# ArduinoCurveTracer3_V1.net
KiCad netlist of a schematic drawn in EAGLE
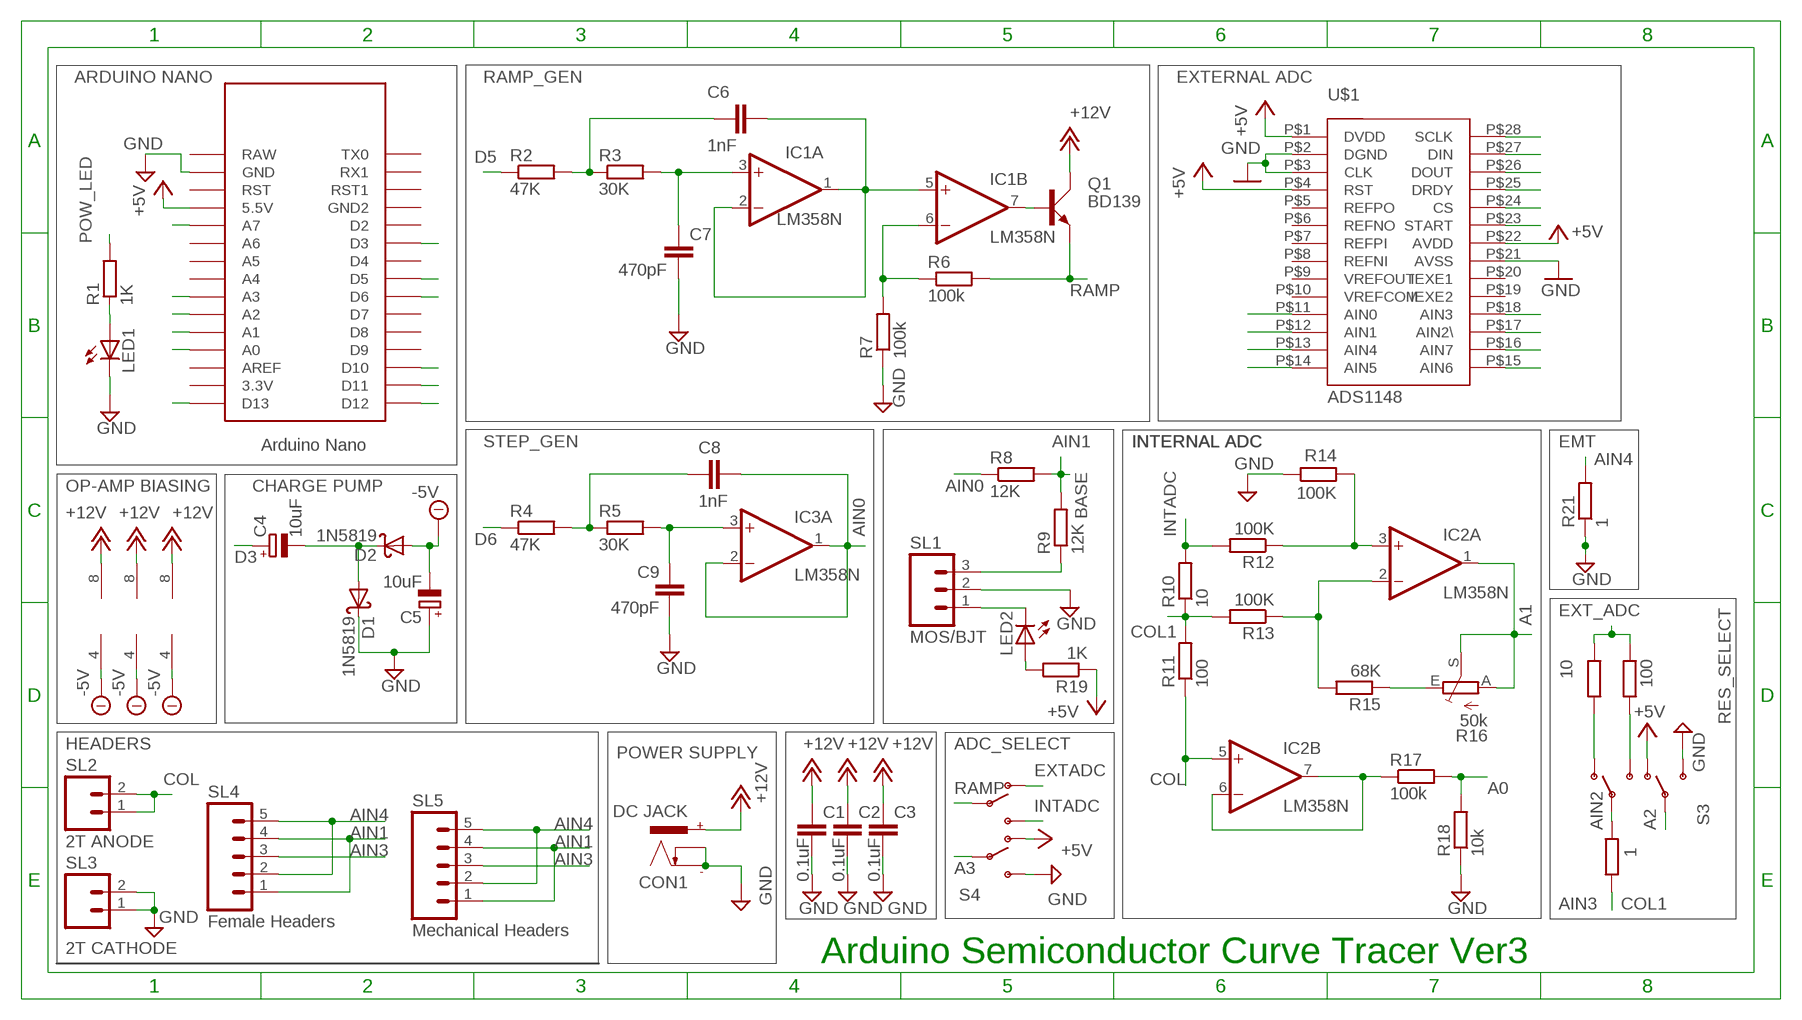
[diagram p0: schematic, sheet 1]

(export (version "E")
  (design (tool "Eeschema 10.0.6"))
  (components
    (comp (ref "ARDUINONANO")
      (value "NANO")
      (footprint "eagle-import:NANO")
      (libsource (lib "eagle-import") (part "NANO"))
    )
    (comp (ref "C1")
      (value "0.1uF")
      (footprint "eagle-import:C0805")
      (libsource (lib "eagle-import") (part "C-EUC0805"))
    )
    (comp (ref "C2")
      (value "0.1uF")
      (footprint "eagle-import:C0805")
      (libsource (lib "eagle-import") (part "C-EUC0805"))
    )
    (comp (ref "C3")
      (value "0.1uF")
      (footprint "eagle-import:C0805")
      (libsource (lib "eagle-import") (part "C-EUC0805"))
    )
    (comp (ref "C4")
      (value "10uF")
      (footprint "eagle-import:E2,5-5")
      (libsource (lib "eagle-import") (part "CPOL-EUE2.5-5"))
    )
    (comp (ref "C5")
      (value "10uF")
      (footprint "eagle-import:E2,5-5")
      (libsource (lib "eagle-import") (part "CPOL-EUE2.5-5"))
    )
    (comp (ref "C6")
      (value "1nF")
      (footprint "eagle-import:C0603")
      (libsource (lib "eagle-import") (part "C-EUC0603"))
    )
    (comp (ref "C7")
      (value "470pF")
      (footprint "eagle-import:C025-024X044")
      (libsource (lib "eagle-import") (part "C-EU025-024X044"))
    )
    (comp (ref "C8")
      (value "1nF")
      (footprint "eagle-import:C025-024X044")
      (libsource (lib "eagle-import") (part "C-EU025-024X044"))
    )
    (comp (ref "C9")
      (value "470pF")
      (footprint "eagle-import:C0805")
      (libsource (lib "eagle-import") (part "C-EUC0805"))
    )
    (comp (ref "CON1")
      (value "DC JACK")
      (footprint "eagle-import:NEB21R")
      (libsource (lib "eagle-import") (part "POWER_CON"))
    )
    (comp (ref "D1")
      (value "1N5819")
      (footprint "eagle-import:DO41-10")
      (libsource (lib "eagle-import") (part "1N5819"))
    )
    (comp (ref "D2")
      (value "1N5819")
      (footprint "eagle-import:DO41-10")
      (libsource (lib "eagle-import") (part "1N5819"))
    )
    (comp (ref "IC1")
      (value "LM358N")
      (footprint "eagle-import:DIL08")
      (libsource (lib "eagle-import") (part "LM358N"))
    )
    (comp (ref "IC2")
      (value "LM358N")
      (footprint "eagle-import:DIL08")
      (libsource (lib "eagle-import") (part "LM358N"))
    )
    (comp (ref "IC3")
      (value "LM358N")
      (footprint "eagle-import:DIL08")
      (libsource (lib "eagle-import") (part "LM358N"))
    )
    (comp (ref "LED1")
      (value "LED3MM")
      (footprint "eagle-import:LED3MM")
      (libsource (lib "eagle-import") (part "LED3MM"))
    )
    (comp (ref "LED2")
      (value "LED3MM")
      (footprint "eagle-import:LED3MM")
      (libsource (lib "eagle-import") (part "LED3MM"))
    )
    (comp (ref "Q1")
      (value "BD139")
      (footprint "eagle-import:TO126AV")
      (libsource (lib "eagle-import") (part "BD139"))
    )
    (comp (ref "R1")
      (value "1K")
      (footprint "eagle-import:0207_10")
      (libsource (lib "eagle-import") (part "rcl_334_R-EU_0207/10"))
    )
    (comp (ref "R2")
      (value "47K")
      (footprint "eagle-import:0207_10")
      (libsource (lib "eagle-import") (part "rcl_334_R-EU_0207/10"))
    )
    (comp (ref "R3")
      (value "30K")
      (footprint "eagle-import:0204_7")
      (libsource (lib "eagle-import") (part "rcl_334_R-EU_0204/7"))
    )
    (comp (ref "R4")
      (value "47K")
      (footprint "eagle-import:0204_7")
      (libsource (lib "eagle-import") (part "rcl_334_R-EU_0204/7"))
    )
    (comp (ref "R5")
      (value "30K")
      (footprint "eagle-import:0204_7")
      (libsource (lib "eagle-import") (part "rcl_334_R-EU_0204/7"))
    )
    (comp (ref "R6")
      (value "100k")
      (footprint "eagle-import:M0805")
      (libsource (lib "eagle-import") (part "R-EU_M0805"))
    )
    (comp (ref "R7")
      (value "100k")
      (footprint "eagle-import:0207_7")
      (libsource (lib "eagle-import") (part "R-EU_0207/7"))
    )
    (comp (ref "R8")
      (value "12K")
      (footprint "eagle-import:0207_10")
      (libsource (lib "eagle-import") (part "resistor_348_R-EU_0207/10"))
    )
    (comp (ref "R9")
      (value "12K")
      (footprint "eagle-import:0207_10")
      (libsource (lib "eagle-import") (part "resistor_348_R-EU_0207/10"))
    )
    (comp (ref "R10")
      (value "10")
      (footprint "eagle-import:0207_10")
      (libsource (lib "eagle-import") (part "rcl_334_R-EU_0207/10"))
    )
    (comp (ref "R11")
      (value "100")
      (footprint "eagle-import:0207_10")
      (libsource (lib "eagle-import") (part "resistor_348_R-EU_0207/10"))
    )
    (comp (ref "R12")
      (value "100K")
      (footprint "eagle-import:0207_10")
      (libsource (lib "eagle-import") (part "rcl_334_R-EU_0207/10"))
    )
    (comp (ref "R13")
      (value "100K")
      (footprint "eagle-import:0207_10")
      (libsource (lib "eagle-import") (part "rcl_334_R-EU_0207/10"))
    )
    (comp (ref "R14")
      (value "100K")
      (footprint "eagle-import:0204_7")
      (libsource (lib "eagle-import") (part "rcl_334_R-EU_0204/7"))
    )
    (comp (ref "R15")
      (value "68K")
      (footprint "eagle-import:0204_7")
      (libsource (lib "eagle-import") (part "rcl_334_R-EU_0204/7"))
    )
    (comp (ref "R16")
      (value "50k")
      (footprint "eagle-import:S64W")
      (libsource (lib "eagle-import") (part "TRIM_EU-S64W"))
    )
    (comp (ref "R17")
      (value "100k")
      (footprint "eagle-import:0207_7")
      (libsource (lib "eagle-import") (part "R-EU_0207/7"))
    )
    (comp (ref "R18")
      (value "10k")
      (footprint "eagle-import:0204_7")
      (libsource (lib "eagle-import") (part "rcl_334_R-EU_0204/7"))
    )
    (comp (ref "R19")
      (value "1K")
      (footprint "eagle-import:0207_10")
      (libsource (lib "eagle-import") (part "rcl_334_R-EU_0207/10"))
    )
    (comp (ref "R21")
      (value "1")
      (footprint "eagle-import:0207_10")
      (libsource (lib "eagle-import") (part "rcl_334_R-EU_0207/10"))
    )
    (comp (ref "R22")
      (value "10")
      (footprint "eagle-import:0204_7")
      (libsource (lib "eagle-import") (part "rcl_334_R-EU_0204/7"))
    )
    (comp (ref "R23")
      (value "100")
      (footprint "eagle-import:0204_7")
      (libsource (lib "eagle-import") (part "rcl_334_R-EU_0204/7"))
    )
    (comp (ref "R24")
      (value "1")
      (footprint "eagle-import:0204_7")
      (libsource (lib "eagle-import") (part "rcl_334_R-EU_0204/7"))
    )
    (comp (ref "S3")
      (value "SWITCH-SPDTPTH2")
      (footprint "eagle-import:SWITCHE-DPDT")
      (libsource (lib "eagle-import") (part "SWITCH-SPDTPTH2"))
    )
    (comp (ref "S4")
      (value "SWITCH-SPDTPTH2")
      (footprint "eagle-import:SWITCHE-DPDT")
      (libsource (lib "eagle-import") (part "SWITCH-SPDTPTH2"))
    )
    (comp (ref "SL1")
      (value "MOS/BJT")
      (footprint "eagle-import:03P")
      (libsource (lib "eagle-import") (part "M03"))
    )
    (comp (ref "SL2")
      (value "2T ANODE")
      (footprint "eagle-import:02P")
      (libsource (lib "eagle-import") (part "M02"))
    )
    (comp (ref "SL3")
      (value "2T CATHODE")
      (footprint "eagle-import:02P")
      (libsource (lib "eagle-import") (part "M02"))
    )
    (comp (ref "SL4")
      (value "Female Headers")
      (footprint "eagle-import:05P")
      (libsource (lib "eagle-import") (part "M05"))
    )
    (comp (ref "SL5")
      (value "Mechanical Headers")
      (footprint "eagle-import:05P")
      (libsource (lib "eagle-import") (part "M05"))
    )
    (comp (ref "U$1")
      (value "ADS1148")
      (footprint "eagle-import:TSSOP-28")
      (libsource (lib "eagle-import") (part "ADS1148"))
    )
  )
  (nets
    (net (code "1") (name "+5V") (class "Default")
      (node (ref "ARDUINONANO") (pin "5V") (pinfunction "5.5V_5V") (pintype "bidirectional"))
      (node (ref "R19") (pin "1") (pinfunction "1_1") (pintype "passive"))
      (node (ref "S3") (pin "4") (pinfunction "4_4") (pintype "passive"))
      (node (ref "S4") (pin "4") (pinfunction "4_4") (pintype "passive"))
      (node (ref "U$1") (pin "P$1") (pinfunction "DVDD_P$1") (pintype "bidirectional"))
      (node (ref "U$1") (pin "P$22") (pinfunction "AVDD_P$22") (pintype "bidirectional"))
      (node (ref "U$1") (pin "P$4") (pinfunction "RST_P$4") (pintype "bidirectional"))
    )
    (net (code "2") (name "+12V") (class "Default")
      (node (ref "C1") (pin "1") (pinfunction "1_1") (pintype "passive"))
      (node (ref "C2") (pin "1") (pinfunction "1_1") (pintype "passive"))
      (node (ref "C3") (pin "1") (pinfunction "1_1") (pintype "passive"))
      (node (ref "CON1") (pin "+") (pinfunction "+_+") (pintype "passive"))
      (node (ref "IC1") (pin "8") (pinfunction "V+_8") (pintype "power_in"))
      (node (ref "IC2") (pin "8") (pinfunction "V+_8") (pintype "power_in"))
      (node (ref "IC3") (pin "8") (pinfunction "V+_8") (pintype "power_in"))
      (node (ref "Q1") (pin "C") (pinfunction "C_C") (pintype "passive"))
    )
    (net (code "3") (name "-5V") (class "Default")
      (node (ref "C5") (pin "-") (pinfunction "-_-") (pintype "passive"))
      (node (ref "D2") (pin "A") (pinfunction "A_A") (pintype "passive"))
      (node (ref "IC1") (pin "4") (pinfunction "V-_4") (pintype "power_in"))
      (node (ref "IC2") (pin "4") (pinfunction "V-_4") (pintype "power_in"))
      (node (ref "IC3") (pin "4") (pinfunction "V-_4") (pintype "power_in"))
    )
    (net (code "4") (name "/A0") (class "Default")
      (node (ref "ARDUINONANO") (pin "A0") (pinfunction "A0_A0") (pintype "bidirectional"))
      (node (ref "R17") (pin "2") (pinfunction "2_2") (pintype "passive"))
      (node (ref "R18") (pin "2") (pinfunction "2_2") (pintype "passive"))
    )
    (net (code "5") (name "/A1") (class "Default")
      (node (ref "ARDUINONANO") (pin "A1") (pinfunction "A1_A1") (pintype "bidirectional"))
      (node (ref "IC2") (pin "1") (pinfunction "OUT_1") (pintype "output"))
      (node (ref "R16") (pin "A") (pinfunction "A_A") (pintype "passive"))
      (node (ref "R16") (pin "S") (pinfunction "S_S") (pintype "passive"))
    )
    (net (code "6") (name "/A2") (class "Default")
      (node (ref "ARDUINONANO") (pin "A2") (pinfunction "A2_A2") (pintype "bidirectional"))
      (node (ref "S3") (pin "5") (pinfunction "5_5") (pintype "passive"))
    )
    (net (code "7") (name "/A3") (class "Default")
      (node (ref "ARDUINONANO") (pin "A3") (pinfunction "A3_A3") (pintype "bidirectional"))
      (node (ref "S4") (pin "5") (pinfunction "5_5") (pintype "passive"))
    )
    (net (code "8") (name "/AIN0") (class "Default")
      (node (ref "C8") (pin "2") (pinfunction "2_2") (pintype "passive"))
      (node (ref "IC3") (pin "1") (pinfunction "OUT_1") (pintype "output"))
      (node (ref "IC3") (pin "2") (pinfunction "-IN_2") (pintype "input"))
      (node (ref "R8") (pin "1") (pinfunction "1_1") (pintype "passive"))
      (node (ref "U$1") (pin "P$11") (pinfunction "AIN0_P$11") (pintype "bidirectional"))
    )
    (net (code "9") (name "/AIN1") (class "Default")
      (node (ref "R8") (pin "2") (pinfunction "2_2") (pintype "passive"))
      (node (ref "R9") (pin "2") (pinfunction "2_2") (pintype "passive"))
      (node (ref "SL4") (pin "1") (pinfunction "1_1") (pintype "passive"))
      (node (ref "SL4") (pin "4") (pinfunction "4_4") (pintype "passive"))
      (node (ref "SL5") (pin "1") (pinfunction "1_1") (pintype "passive"))
      (node (ref "SL5") (pin "4") (pinfunction "4_4") (pintype "passive"))
      (node (ref "U$1") (pin "P$12") (pinfunction "AIN1_P$12") (pintype "bidirectional"))
    )
    (net (code "10") (name "/AIN2") (class "Default")
      (node (ref "R24") (pin "1") (pinfunction "1_1") (pintype "passive"))
      (node (ref "S3") (pin "2") (pinfunction "2_2") (pintype "passive"))
      (node (ref "U$1") (pin "P$17") (pinfunction "AIN2\\_P$17") (pintype "bidirectional"))
    )
    (net (code "11") (name "/AIN3") (class "Default")
      (node (ref "R10") (pin "1") (pinfunction "1_1") (pintype "passive"))
      (node (ref "R11") (pin "2") (pinfunction "2_2") (pintype "passive"))
      (node (ref "R13") (pin "2") (pinfunction "2_2") (pintype "passive"))
      (node (ref "R24") (pin "2") (pinfunction "2_2") (pintype "passive"))
      (node (ref "SL4") (pin "3") (pinfunction "3_3") (pintype "passive"))
      (node (ref "SL5") (pin "3") (pinfunction "3_3") (pintype "passive"))
      (node (ref "U$1") (pin "P$18") (pinfunction "AIN3_P$18") (pintype "bidirectional"))
    )
    (net (code "12") (name "/AIN4") (class "Default")
      (node (ref "R21") (pin "2") (pinfunction "2_2") (pintype "passive"))
      (node (ref "SL4") (pin "2") (pinfunction "2_2") (pintype "passive"))
      (node (ref "SL4") (pin "5") (pinfunction "5_5") (pintype "passive"))
      (node (ref "SL5") (pin "2") (pinfunction "2_2") (pintype "passive"))
      (node (ref "SL5") (pin "5") (pinfunction "5_5") (pintype "passive"))
      (node (ref "U$1") (pin "P$13") (pinfunction "AIN4_P$13") (pintype "bidirectional"))
    )
    (net (code "13") (name "/COL") (class "Default")
      (node (ref "IC2") (pin "5") (pinfunction "+IN_5") (pintype "input"))
      (node (ref "R11") (pin "1") (pinfunction "1_1") (pintype "passive"))
      (node (ref "SL2") (pin "1") (pinfunction "1_1") (pintype "passive"))
      (node (ref "SL2") (pin "2") (pinfunction "2_2") (pintype "passive"))
    )
    (net (code "14") (name "/CS") (class "Default")
      (node (ref "ARDUINONANO") (pin "D10") (pinfunction "D10_D10") (pintype "bidirectional"))
      (node (ref "U$1") (pin "P$24") (pinfunction "CS_P$24") (pintype "bidirectional"))
    )
    (net (code "15") (name "/D3") (class "Default")
      (node (ref "ARDUINONANO") (pin "D3") (pinfunction "D3_D3") (pintype "bidirectional"))
      (node (ref "C4") (pin "+") (pinfunction "+_+") (pintype "passive"))
    )
    (net (code "16") (name "/D5") (class "Default")
      (node (ref "ARDUINONANO") (pin "D5") (pinfunction "D5_D5") (pintype "bidirectional"))
      (node (ref "R2") (pin "1") (pinfunction "1_1") (pintype "passive"))
    )
    (net (code "17") (name "/D6") (class "Default")
      (node (ref "ARDUINONANO") (pin "D6") (pinfunction "D6_D6") (pintype "bidirectional"))
      (node (ref "R4") (pin "1") (pinfunction "1_1") (pintype "passive"))
    )
    (net (code "18") (name "/DIN") (class "Default")
      (node (ref "ARDUINONANO") (pin "D11") (pinfunction "D11_D11") (pintype "bidirectional"))
      (node (ref "U$1") (pin "P$27") (pinfunction "DIN_P$27") (pintype "bidirectional"))
    )
    (net (code "19") (name "/DOUT") (class "Default")
      (node (ref "ARDUINONANO") (pin "D12") (pinfunction "D12_D12") (pintype "bidirectional"))
      (node (ref "U$1") (pin "P$26") (pinfunction "DOUT_P$26") (pintype "bidirectional"))
    )
    (net (code "20") (name "/EXTADC") (class "Default")
      (node (ref "R22") (pin "2") (pinfunction "2_2") (pintype "passive"))
      (node (ref "R23") (pin "2") (pinfunction "2_2") (pintype "passive"))
      (node (ref "S4") (pin "1") (pinfunction "1_1") (pintype "passive"))
    )
    (net (code "21") (name "/INTADC") (class "Default")
      (node (ref "R10") (pin "2") (pinfunction "2_2") (pintype "passive"))
      (node (ref "R12") (pin "2") (pinfunction "2_2") (pintype "passive"))
      (node (ref "S4") (pin "3") (pinfunction "3_3") (pintype "passive"))
    )
    (net (code "22") (name "/POW_LED") (class "Default")
      (node (ref "ARDUINONANO") (pin "A7") (pinfunction "A7_A7") (pintype "bidirectional"))
      (node (ref "R1") (pin "2") (pinfunction "2_2") (pintype "passive"))
    )
    (net (code "23") (name "/RAMP") (class "Default")
      (node (ref "C6") (pin "2") (pinfunction "2_2") (pintype "passive"))
      (node (ref "IC1") (pin "1") (pinfunction "OUT_1") (pintype "output"))
      (node (ref "IC1") (pin "2") (pinfunction "-IN_2") (pintype "input"))
      (node (ref "IC1") (pin "5") (pinfunction "+IN_5") (pintype "input"))
      (node (ref "Q1") (pin "E") (pinfunction "E_E") (pintype "passive"))
      (node (ref "R6") (pin "2") (pinfunction "2_2") (pintype "passive"))
      (node (ref "S4") (pin "2") (pinfunction "2_2") (pintype "passive"))
    )
    (net (code "24") (name "/SCLK") (class "Default")
      (node (ref "ARDUINONANO") (pin "D13") (pinfunction "D13_D13") (pintype "bidirectional"))
      (node (ref "U$1") (pin "P$28") (pinfunction "SCLK_P$28") (pintype "bidirectional"))
    )
    (net (code "25") (name "GND") (class "Default")
      (node (ref "ARDUINONANO") (pin "GND") (pinfunction "GND_GND") (pintype "bidirectional"))
      (node (ref "C1") (pin "2") (pinfunction "2_2") (pintype "passive"))
      (node (ref "C2") (pin "2") (pinfunction "2_2") (pintype "passive"))
      (node (ref "C3") (pin "2") (pinfunction "2_2") (pintype "passive"))
      (node (ref "C5") (pin "+") (pinfunction "+_+") (pintype "passive"))
      (node (ref "C7") (pin "2") (pinfunction "2_2") (pintype "passive"))
      (node (ref "C9") (pin "1") (pinfunction "1_1") (pintype "passive"))
      (node (ref "CON1") (pin "-") (pinfunction "-_-") (pintype "passive"))
      (node (ref "CON1") (pin "C") (pinfunction "C_C") (pintype "passive"))
      (node (ref "D1") (pin "C") (pinfunction "C_C") (pintype "passive"))
      (node (ref "LED1") (pin "K") (pinfunction "C_K") (pintype "passive"))
      (node (ref "R14") (pin "1") (pinfunction "1_1") (pintype "passive"))
      (node (ref "R18") (pin "1") (pinfunction "1_1") (pintype "passive"))
      (node (ref "R21") (pin "1") (pinfunction "1_1") (pintype "passive"))
      (node (ref "R7") (pin "1") (pinfunction "1_1") (pintype "passive"))
      (node (ref "S3") (pin "6") (pinfunction "6_6") (pintype "passive"))
      (node (ref "S4") (pin "6") (pinfunction "6_6") (pintype "passive"))
      (node (ref "SL1") (pin "2") (pinfunction "2_2") (pintype "passive"))
      (node (ref "SL3") (pin "1") (pinfunction "1_1") (pintype "passive"))
      (node (ref "SL3") (pin "2") (pinfunction "2_2") (pintype "passive"))
      (node (ref "U$1") (pin "P$2") (pinfunction "DGND_P$2") (pintype "bidirectional"))
      (node (ref "U$1") (pin "P$21") (pinfunction "AVSS_P$21") (pintype "bidirectional"))
      (node (ref "U$1") (pin "P$3") (pinfunction "CLK_P$3") (pintype "bidirectional"))
    )
    (net (code "26") (name "Net-(C4-Pad-)") (class "Default")
      (node (ref "C4") (pin "-") (pinfunction "-_-") (pintype "passive"))
      (node (ref "D1") (pin "A") (pinfunction "A_A") (pintype "passive"))
      (node (ref "D2") (pin "C") (pinfunction "C_C") (pintype "passive"))
    )
    (net (code "27") (name "Net-(C6-Pad1)") (class "Default")
      (node (ref "C6") (pin "1") (pinfunction "1_1") (pintype "passive"))
      (node (ref "R2") (pin "2") (pinfunction "2_2") (pintype "passive"))
      (node (ref "R3") (pin "1") (pinfunction "1_1") (pintype "passive"))
    )
    (net (code "28") (name "Net-(C8-Pad1)") (class "Default")
      (node (ref "C8") (pin "1") (pinfunction "1_1") (pintype "passive"))
      (node (ref "R4") (pin "2") (pinfunction "2_2") (pintype "passive"))
      (node (ref "R5") (pin "1") (pinfunction "1_1") (pintype "passive"))
    )
    (net (code "29") (name "Net-(IC1A-+IN)") (class "Default")
      (node (ref "C7") (pin "1") (pinfunction "1_1") (pintype "passive"))
      (node (ref "IC1") (pin "3") (pinfunction "+IN_3") (pintype "input"))
      (node (ref "R3") (pin "2") (pinfunction "2_2") (pintype "passive"))
    )
    (net (code "30") (name "Net-(IC1B--IN)") (class "Default")
      (node (ref "IC1") (pin "6") (pinfunction "-IN_6") (pintype "input"))
      (node (ref "R6") (pin "1") (pinfunction "1_1") (pintype "passive"))
      (node (ref "R7") (pin "2") (pinfunction "2_2") (pintype "passive"))
    )
    (net (code "31") (name "Net-(IC1B-OUT)") (class "Default")
      (node (ref "IC1") (pin "7") (pinfunction "OUT_7") (pintype "output"))
      (node (ref "Q1") (pin "B") (pinfunction "B_B") (pintype "passive"))
    )
    (net (code "32") (name "Net-(IC2A-+IN)") (class "Default")
      (node (ref "IC2") (pin "3") (pinfunction "+IN_3") (pintype "input"))
      (node (ref "R12") (pin "1") (pinfunction "1_1") (pintype "passive"))
      (node (ref "R14") (pin "2") (pinfunction "2_2") (pintype "passive"))
    )
    (net (code "33") (name "Net-(IC2A--IN)") (class "Default")
      (node (ref "IC2") (pin "2") (pinfunction "-IN_2") (pintype "input"))
      (node (ref "R13") (pin "1") (pinfunction "1_1") (pintype "passive"))
      (node (ref "R15") (pin "2") (pinfunction "2_2") (pintype "passive"))
    )
    (net (code "34") (name "Net-(IC2B--IN)") (class "Default")
      (node (ref "IC2") (pin "6") (pinfunction "-IN_6") (pintype "input"))
      (node (ref "IC2") (pin "7") (pinfunction "OUT_7") (pintype "output"))
      (node (ref "R17") (pin "1") (pinfunction "1_1") (pintype "passive"))
    )
    (net (code "35") (name "Net-(IC3A-+IN)") (class "Default")
      (node (ref "C9") (pin "2") (pinfunction "2_2") (pintype "passive"))
      (node (ref "IC3") (pin "3") (pinfunction "+IN_3") (pintype "input"))
      (node (ref "R5") (pin "2") (pinfunction "2_2") (pintype "passive"))
    )
    (net (code "36") (name "Net-(LED1-PadA)") (class "Default")
      (node (ref "LED1") (pin "A") (pinfunction "A_A") (pintype "passive"))
      (node (ref "R1") (pin "1") (pinfunction "1_1") (pintype "passive"))
    )
    (net (code "37") (name "Net-(LED2-C)") (class "Default")
      (node (ref "LED2") (pin "K") (pinfunction "C_K") (pintype "passive"))
      (node (ref "SL1") (pin "1") (pinfunction "1_1") (pintype "passive"))
    )
    (net (code "38") (name "Net-(LED2-PadA)") (class "Default")
      (node (ref "LED2") (pin "A") (pinfunction "A_A") (pintype "passive"))
      (node (ref "R19") (pin "2") (pinfunction "2_2") (pintype "passive"))
    )
    (net (code "39") (name "Net-(R9-Pad1)") (class "Default")
      (node (ref "R9") (pin "1") (pinfunction "1_1") (pintype "passive"))
      (node (ref "SL1") (pin "3") (pinfunction "3_3") (pintype "passive"))
    )
    (net (code "40") (name "Net-(R15-Pad1)") (class "Default")
      (node (ref "R15") (pin "1") (pinfunction "1_1") (pintype "passive"))
      (node (ref "R16") (pin "E") (pinfunction "E_E") (pintype "passive"))
    )
    (net (code "41") (name "Net-(R22-Pad1)") (class "Default")
      (node (ref "R22") (pin "1") (pinfunction "1_1") (pintype "passive"))
      (node (ref "S3") (pin "1") (pinfunction "1_1") (pintype "passive"))
    )
    (net (code "42") (name "Net-(R23-Pad1)") (class "Default")
      (node (ref "R23") (pin "1") (pinfunction "1_1") (pintype "passive"))
      (node (ref "S3") (pin "3") (pinfunction "3_3") (pintype "passive"))
    )
    (net (code "43") (name "unconnected-(ARDUINONANO-GND2-PadGND1)") (class "Default")
      (node (ref "ARDUINONANO") (pin "GND1") (pinfunction "GND2_GND1") (pintype "bidirectional"))
    )
    (net (code "44") (name "unconnected-(ARDUINONANO-Pad3.3V)") (class "Default")
      (node (ref "ARDUINONANO") (pin "3.3V") (pinfunction "3.3V_3.3V") (pintype "bidirectional"))
    )
    (net (code "45") (name "unconnected-(ARDUINONANO-PadA4)") (class "Default")
      (node (ref "ARDUINONANO") (pin "A4") (pinfunction "A4_A4") (pintype "bidirectional"))
    )
    (net (code "46") (name "unconnected-(ARDUINONANO-PadA5)") (class "Default")
      (node (ref "ARDUINONANO") (pin "A5") (pinfunction "A5_A5") (pintype "bidirectional"))
    )
    (net (code "47") (name "unconnected-(ARDUINONANO-PadA6)") (class "Default")
      (node (ref "ARDUINONANO") (pin "A6") (pinfunction "A6_A6") (pintype "bidirectional"))
    )
    (net (code "48") (name "unconnected-(ARDUINONANO-PadAREF)") (class "Default")
      (node (ref "ARDUINONANO") (pin "AREF") (pinfunction "AREF_AREF") (pintype "bidirectional"))
    )
    (net (code "49") (name "unconnected-(ARDUINONANO-PadD2)") (class "Default")
      (node (ref "ARDUINONANO") (pin "D2") (pinfunction "D2_D2") (pintype "bidirectional"))
    )
    (net (code "50") (name "unconnected-(ARDUINONANO-PadD4)") (class "Default")
      (node (ref "ARDUINONANO") (pin "D4") (pinfunction "D4_D4") (pintype "bidirectional"))
    )
    (net (code "51") (name "unconnected-(ARDUINONANO-PadD7)") (class "Default")
      (node (ref "ARDUINONANO") (pin "D7") (pinfunction "D7_D7") (pintype "bidirectional"))
    )
    (net (code "52") (name "unconnected-(ARDUINONANO-PadD8)") (class "Default")
      (node (ref "ARDUINONANO") (pin "D8") (pinfunction "D8_D8") (pintype "bidirectional"))
    )
    (net (code "53") (name "unconnected-(ARDUINONANO-PadD9)") (class "Default")
      (node (ref "ARDUINONANO") (pin "D9") (pinfunction "D9_D9") (pintype "bidirectional"))
    )
    (net (code "54") (name "unconnected-(ARDUINONANO-PadRAW)") (class "Default")
      (node (ref "ARDUINONANO") (pin "RAW") (pinfunction "RAW_RAW") (pintype "bidirectional"))
    )
    (net (code "55") (name "unconnected-(ARDUINONANO-PadRST)") (class "Default")
      (node (ref "ARDUINONANO") (pin "RST") (pinfunction "RST_RST") (pintype "bidirectional"))
    )
    (net (code "56") (name "unconnected-(ARDUINONANO-PadRST1)") (class "Default")
      (node (ref "ARDUINONANO") (pin "RST1") (pinfunction "RST1_RST1") (pintype "bidirectional"))
    )
    (net (code "57") (name "unconnected-(ARDUINONANO-PadRX1)") (class "Default")
      (node (ref "ARDUINONANO") (pin "RX1") (pinfunction "RX1_RX1") (pintype "bidirectional"))
    )
    (net (code "58") (name "unconnected-(ARDUINONANO-PadTX0)") (class "Default")
      (node (ref "ARDUINONANO") (pin "TX0") (pinfunction "TX0_TX0") (pintype "bidirectional"))
    )
    (net (code "59") (name "unconnected-(U$1-AIN5-PadP$14)") (class "Default")
      (node (ref "U$1") (pin "P$14") (pinfunction "AIN5_P$14") (pintype "bidirectional"))
    )
    (net (code "60") (name "unconnected-(U$1-AIN6-PadP$15)") (class "Default")
      (node (ref "U$1") (pin "P$15") (pinfunction "AIN6_P$15") (pintype "bidirectional"))
    )
    (net (code "61") (name "unconnected-(U$1-AIN7-PadP$16)") (class "Default")
      (node (ref "U$1") (pin "P$16") (pinfunction "AIN7_P$16") (pintype "bidirectional"))
    )
    (net (code "62") (name "unconnected-(U$1-DRDY-PadP$25)") (class "Default")
      (node (ref "U$1") (pin "P$25") (pinfunction "DRDY_P$25") (pintype "bidirectional"))
    )
    (net (code "63") (name "unconnected-(U$1-IEXE1-PadP$20)") (class "Default")
      (node (ref "U$1") (pin "P$20") (pinfunction "IEXE1_P$20") (pintype "bidirectional"))
    )
    (net (code "64") (name "unconnected-(U$1-IEXE2-PadP$19)") (class "Default")
      (node (ref "U$1") (pin "P$19") (pinfunction "IEXE2_P$19") (pintype "bidirectional"))
    )
    (net (code "65") (name "unconnected-(U$1-REFNI-PadP$8)") (class "Default")
      (node (ref "U$1") (pin "P$8") (pinfunction "REFNI_P$8") (pintype "bidirectional"))
    )
    (net (code "66") (name "unconnected-(U$1-REFNO-PadP$6)") (class "Default")
      (node (ref "U$1") (pin "P$6") (pinfunction "REFNO_P$6") (pintype "bidirectional"))
    )
    (net (code "67") (name "unconnected-(U$1-REFPI-PadP$7)") (class "Default")
      (node (ref "U$1") (pin "P$7") (pinfunction "REFPI_P$7") (pintype "bidirectional"))
    )
    (net (code "68") (name "unconnected-(U$1-REFPO-PadP$5)") (class "Default")
      (node (ref "U$1") (pin "P$5") (pinfunction "REFPO_P$5") (pintype "bidirectional"))
    )
    (net (code "69") (name "unconnected-(U$1-START-PadP$23)") (class "Default")
      (node (ref "U$1") (pin "P$23") (pinfunction "START_P$23") (pintype "bidirectional"))
    )
    (net (code "70") (name "unconnected-(U$1-VREFCOM-PadP$10)") (class "Default")
      (node (ref "U$1") (pin "P$10") (pinfunction "VREFCOM_P$10") (pintype "bidirectional"))
    )
    (net (code "71") (name "unconnected-(U$1-VREFOUT-PadP$9)") (class "Default")
      (node (ref "U$1") (pin "P$9") (pinfunction "VREFOUT_P$9") (pintype "bidirectional"))
    )
  )
)
